# M117B.net
KiCad netlist of a schematic drawn in EAGLE
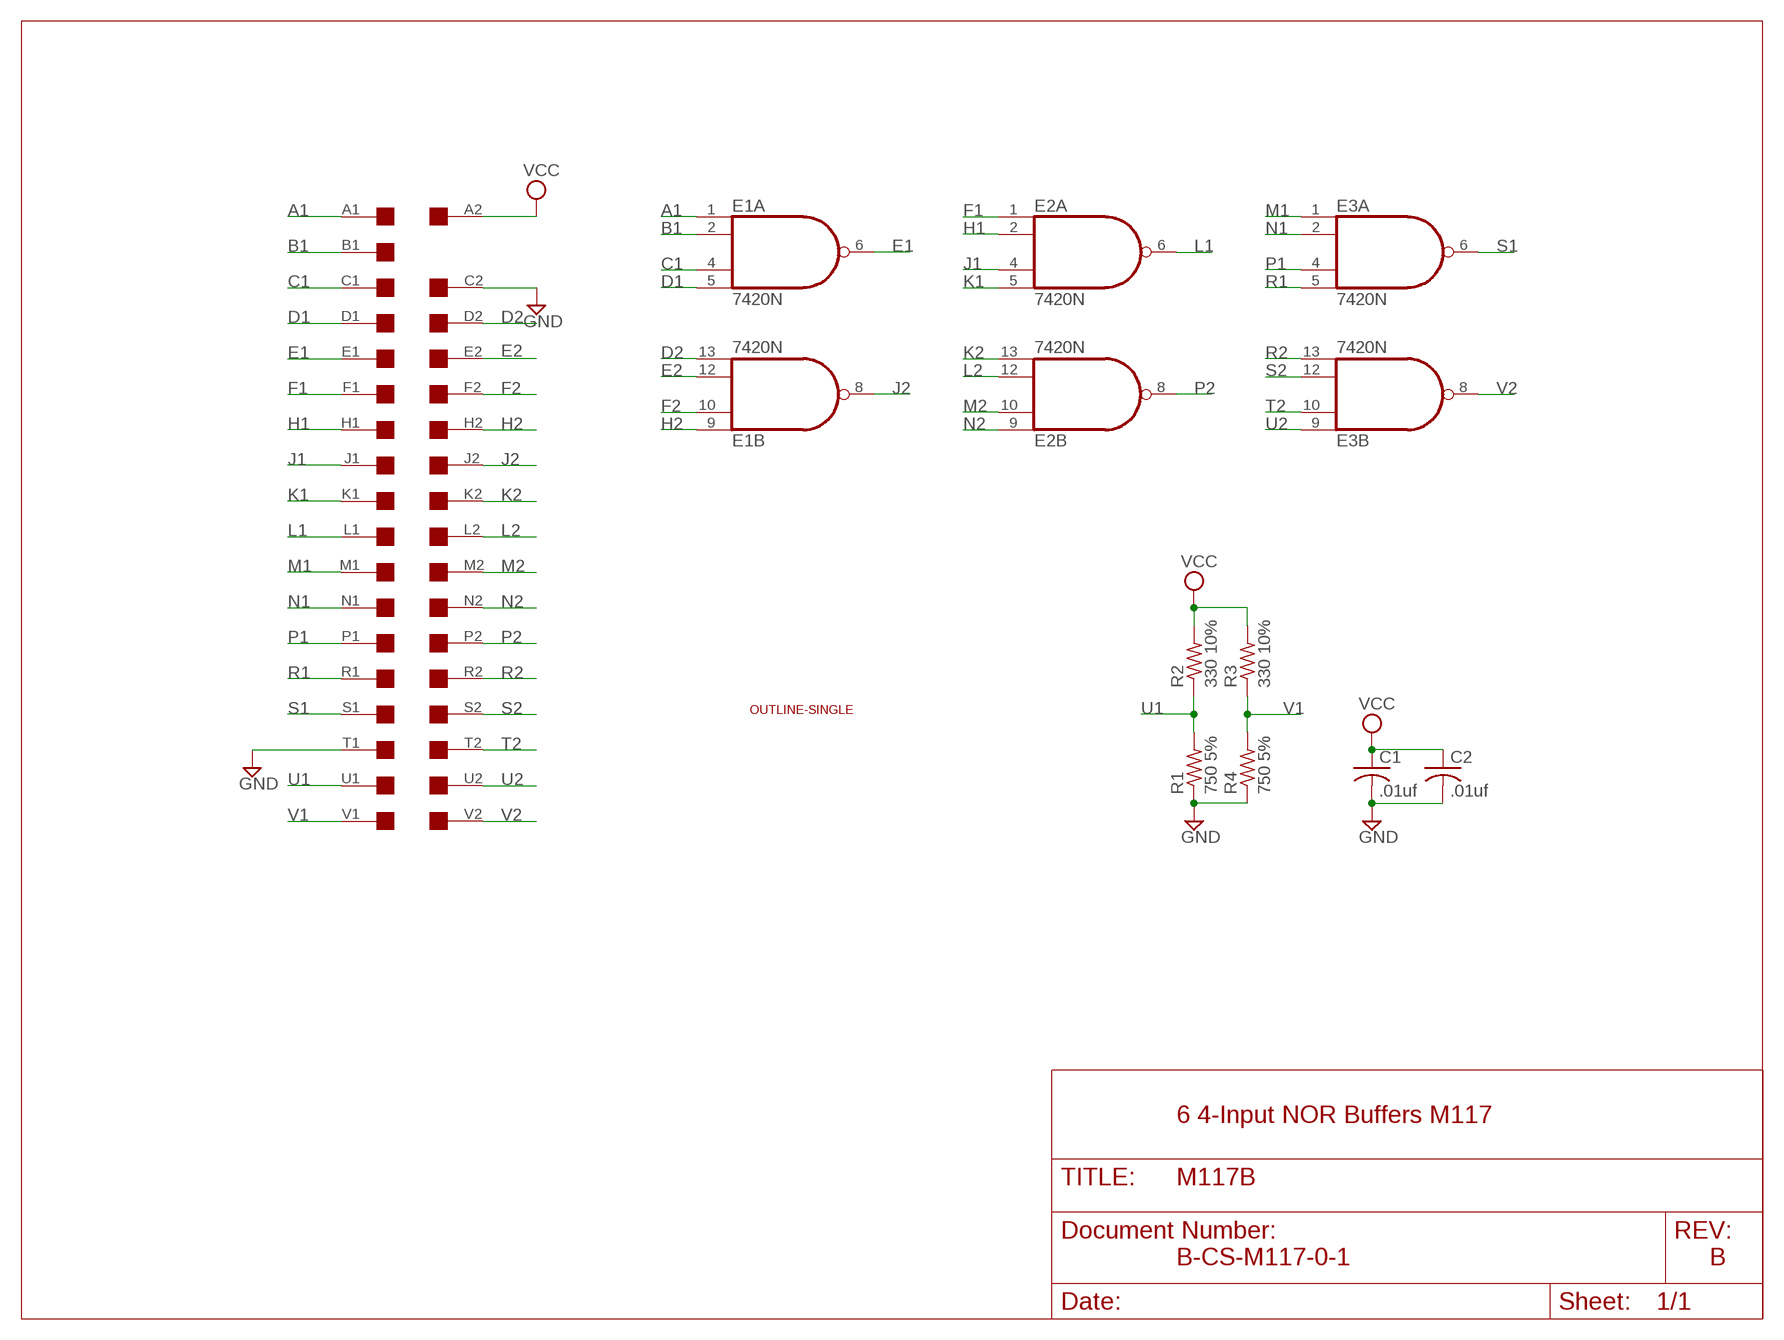
[diagram p0: schematic, sheet 1]

(export (version "E")
  (design (tool "Eeschema 10.0.6"))
  (components
    (comp (ref "C1")
      (value ".01uf")
      (footprint "eagle-import:C075-032X103")
      (libsource (lib "eagle-import") (part "C-US075-032X103"))
    )
    (comp (ref "C2")
      (value ".01uf")
      (footprint "eagle-import:C075-032X103")
      (libsource (lib "eagle-import") (part "C-US075-032X103"))
    )
    (comp (ref "E1")
      (value "7420N")
      (footprint "eagle-import:DIL14")
      (libsource (lib "eagle-import") (part "7420NS"))
    )
    (comp (ref "E2")
      (value "7420N")
      (footprint "eagle-import:DIL14")
      (libsource (lib "eagle-import") (part "7420NS"))
    )
    (comp (ref "E3")
      (value "7420N")
      (footprint "eagle-import:DIL14")
      (libsource (lib "eagle-import") (part "7420NS"))
    )
    (comp (ref "R1")
      (value "750 5%")
      (footprint "eagle-import:0207_15")
      (libsource (lib "eagle-import") (part "R-US_0207/15"))
    )
    (comp (ref "R2")
      (value "330 10%")
      (footprint "eagle-import:0207_15")
      (libsource (lib "eagle-import") (part "R-US_0207/15"))
    )
    (comp (ref "R3")
      (value "330 10%")
      (footprint "eagle-import:0207_15")
      (libsource (lib "eagle-import") (part "R-US_0207/15"))
    )
    (comp (ref "R4")
      (value "750 5%")
      (footprint "eagle-import:0207_15")
      (libsource (lib "eagle-import") (part "R-US_0207/15"))
    )
    (comp (ref "U$1")
      (value "SINGLE")
      (footprint "eagle-import:EDGE-CON2")
      (libsource (lib "eagle-import") (part "SINGLE"))
    )
    (comp (ref "U$4")
      (value "OUTLINE-SINGLE")
      (footprint "eagle-import:SINGLE")
      (libsource (lib "eagle-import") (part "OUTLINE-SINGLE"))
    )
  )
  (nets
    (net (code "1") (name "/A1") (class "Default")
      (node (ref "E1") (pin "1") (pinfunction "I0_1") (pintype "input"))
      (node (ref "U$1") (pin "A1") (pinfunction "1_A1") (pintype "bidirectional"))
    )
    (net (code "2") (name "/B1") (class "Default")
      (node (ref "E1") (pin "2") (pinfunction "I1_2") (pintype "input"))
      (node (ref "U$1") (pin "B1") (pinfunction "1_B1") (pintype "bidirectional"))
    )
    (net (code "3") (name "/C1") (class "Default")
      (node (ref "E1") (pin "4") (pinfunction "I2_4") (pintype "input"))
      (node (ref "U$1") (pin "C1") (pinfunction "1_C1") (pintype "bidirectional"))
    )
    (net (code "4") (name "/D1") (class "Default")
      (node (ref "E1") (pin "5") (pinfunction "I3_5") (pintype "input"))
      (node (ref "U$1") (pin "D1") (pinfunction "1_D1") (pintype "bidirectional"))
    )
    (net (code "5") (name "/D2") (class "Default")
      (node (ref "E1") (pin "13") (pinfunction "I3_13") (pintype "input"))
      (node (ref "U$1") (pin "D2") (pinfunction "1_D2") (pintype "bidirectional"))
    )
    (net (code "6") (name "/E1") (class "Default")
      (node (ref "E1") (pin "6") (pinfunction "O_6") (pintype "output"))
      (node (ref "U$1") (pin "E1") (pinfunction "1_E1") (pintype "bidirectional"))
    )
    (net (code "7") (name "/E2") (class "Default")
      (node (ref "E1") (pin "12") (pinfunction "I2_12") (pintype "input"))
      (node (ref "U$1") (pin "E2") (pinfunction "1_E2") (pintype "bidirectional"))
    )
    (net (code "8") (name "/F1") (class "Default")
      (node (ref "E2") (pin "1") (pinfunction "I0_1") (pintype "input"))
      (node (ref "U$1") (pin "F1") (pinfunction "1_F1") (pintype "bidirectional"))
    )
    (net (code "9") (name "/F2") (class "Default")
      (node (ref "E1") (pin "10") (pinfunction "I1_10") (pintype "input"))
      (node (ref "U$1") (pin "F2") (pinfunction "1_F2") (pintype "bidirectional"))
    )
    (net (code "10") (name "/H1") (class "Default")
      (node (ref "E2") (pin "2") (pinfunction "I1_2") (pintype "input"))
      (node (ref "U$1") (pin "H1") (pinfunction "1_H1") (pintype "bidirectional"))
    )
    (net (code "11") (name "/H2") (class "Default")
      (node (ref "E1") (pin "9") (pinfunction "I0_9") (pintype "input"))
      (node (ref "U$1") (pin "H2") (pinfunction "1_H2") (pintype "bidirectional"))
    )
    (net (code "12") (name "/J1") (class "Default")
      (node (ref "E2") (pin "4") (pinfunction "I2_4") (pintype "input"))
      (node (ref "U$1") (pin "J1") (pinfunction "1_J1") (pintype "bidirectional"))
    )
    (net (code "13") (name "/J2") (class "Default")
      (node (ref "E1") (pin "8") (pinfunction "O_8") (pintype "output"))
      (node (ref "U$1") (pin "J2") (pinfunction "1_J2") (pintype "bidirectional"))
    )
    (net (code "14") (name "/K1") (class "Default")
      (node (ref "E2") (pin "5") (pinfunction "I3_5") (pintype "input"))
      (node (ref "U$1") (pin "K1") (pinfunction "1_K1") (pintype "bidirectional"))
    )
    (net (code "15") (name "/K2") (class "Default")
      (node (ref "E2") (pin "13") (pinfunction "I3_13") (pintype "input"))
      (node (ref "U$1") (pin "K2") (pinfunction "1_K2") (pintype "bidirectional"))
    )
    (net (code "16") (name "/L1") (class "Default")
      (node (ref "E2") (pin "6") (pinfunction "O_6") (pintype "output"))
      (node (ref "U$1") (pin "L1") (pinfunction "1_L1") (pintype "bidirectional"))
    )
    (net (code "17") (name "/L2") (class "Default")
      (node (ref "E2") (pin "12") (pinfunction "I2_12") (pintype "input"))
      (node (ref "U$1") (pin "L2") (pinfunction "1_L2") (pintype "bidirectional"))
    )
    (net (code "18") (name "/M1") (class "Default")
      (node (ref "E3") (pin "1") (pinfunction "I0_1") (pintype "input"))
      (node (ref "U$1") (pin "M1") (pinfunction "1_M1") (pintype "bidirectional"))
    )
    (net (code "19") (name "/M2") (class "Default")
      (node (ref "E2") (pin "10") (pinfunction "I1_10") (pintype "input"))
      (node (ref "U$1") (pin "M2") (pinfunction "1_M2") (pintype "bidirectional"))
    )
    (net (code "20") (name "/N1") (class "Default")
      (node (ref "E3") (pin "2") (pinfunction "I1_2") (pintype "input"))
      (node (ref "U$1") (pin "N1") (pinfunction "1_N1") (pintype "bidirectional"))
    )
    (net (code "21") (name "/N2") (class "Default")
      (node (ref "E2") (pin "9") (pinfunction "I0_9") (pintype "input"))
      (node (ref "U$1") (pin "N2") (pinfunction "1_N2") (pintype "bidirectional"))
    )
    (net (code "22") (name "/P1") (class "Default")
      (node (ref "E3") (pin "4") (pinfunction "I2_4") (pintype "input"))
      (node (ref "U$1") (pin "P1") (pinfunction "1_P1") (pintype "bidirectional"))
    )
    (net (code "23") (name "/P2") (class "Default")
      (node (ref "E2") (pin "8") (pinfunction "O_8") (pintype "output"))
      (node (ref "U$1") (pin "P2") (pinfunction "1_P2") (pintype "bidirectional"))
    )
    (net (code "24") (name "/R1") (class "Default")
      (node (ref "E3") (pin "5") (pinfunction "I3_5") (pintype "input"))
      (node (ref "U$1") (pin "R1") (pinfunction "1_R1") (pintype "bidirectional"))
    )
    (net (code "25") (name "/R2") (class "Default")
      (node (ref "E3") (pin "13") (pinfunction "I3_13") (pintype "input"))
      (node (ref "U$1") (pin "R2") (pinfunction "1_R2") (pintype "bidirectional"))
    )
    (net (code "26") (name "/S1") (class "Default")
      (node (ref "E3") (pin "6") (pinfunction "O_6") (pintype "output"))
      (node (ref "U$1") (pin "S1") (pinfunction "1_S1") (pintype "bidirectional"))
    )
    (net (code "27") (name "/S2") (class "Default")
      (node (ref "E3") (pin "12") (pinfunction "I2_12") (pintype "input"))
      (node (ref "U$1") (pin "S2") (pinfunction "1_S2") (pintype "bidirectional"))
    )
    (net (code "28") (name "/T2") (class "Default")
      (node (ref "E3") (pin "10") (pinfunction "I1_10") (pintype "input"))
      (node (ref "U$1") (pin "T2") (pinfunction "1_T2") (pintype "bidirectional"))
    )
    (net (code "29") (name "/U1") (class "Default")
      (node (ref "R1") (pin "2") (pinfunction "2_2") (pintype "passive"))
      (node (ref "R2") (pin "1") (pinfunction "1_1") (pintype "passive"))
      (node (ref "U$1") (pin "U1") (pinfunction "1_U1") (pintype "bidirectional"))
    )
    (net (code "30") (name "/U2") (class "Default")
      (node (ref "E3") (pin "9") (pinfunction "I0_9") (pintype "input"))
      (node (ref "U$1") (pin "U2") (pinfunction "1_U2") (pintype "bidirectional"))
    )
    (net (code "31") (name "/V1") (class "Default")
      (node (ref "R3") (pin "1") (pinfunction "1_1") (pintype "passive"))
      (node (ref "R4") (pin "2") (pinfunction "2_2") (pintype "passive"))
      (node (ref "U$1") (pin "V1") (pinfunction "1_V1") (pintype "bidirectional"))
    )
    (net (code "32") (name "/V2") (class "Default")
      (node (ref "E3") (pin "8") (pinfunction "O_8") (pintype "output"))
      (node (ref "U$1") (pin "V2") (pinfunction "1_V2") (pintype "bidirectional"))
    )
    (net (code "33") (name "GND") (class "Default")
      (node (ref "C1") (pin "2") (pinfunction "2_2") (pintype "passive"))
      (node (ref "C2") (pin "2") (pinfunction "2_2") (pintype "passive"))
      (node (ref "R1") (pin "1") (pinfunction "1_1") (pintype "passive"))
      (node (ref "R4") (pin "1") (pinfunction "1_1") (pintype "passive"))
      (node (ref "U$1") (pin "C2") (pinfunction "1_C2") (pintype "bidirectional"))
      (node (ref "U$1") (pin "T1") (pinfunction "1_T1") (pintype "bidirectional"))
    )
    (net (code "34") (name "VCC") (class "Default")
      (node (ref "C1") (pin "1") (pinfunction "1_1") (pintype "passive"))
      (node (ref "C2") (pin "1") (pinfunction "1_1") (pintype "passive"))
      (node (ref "R2") (pin "2") (pinfunction "2_2") (pintype "passive"))
      (node (ref "R3") (pin "2") (pinfunction "2_2") (pintype "passive"))
      (node (ref "U$1") (pin "A2") (pinfunction "1_A2") (pintype "bidirectional"))
    )
  )
)
